# untitled.net
KiCad netlist of a schematic drawn in EAGLE
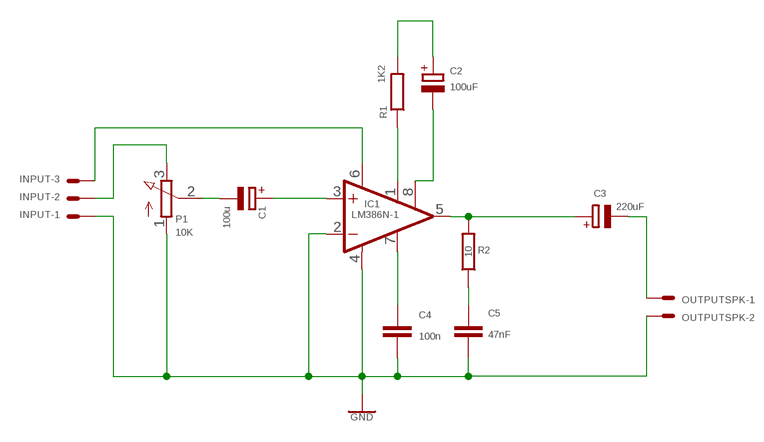
[diagram p0: schematic, sheet 1]

(export (version "E")
  (design (tool "Eeschema 10.0.6"))
  (components
    (comp (ref "C1")
      (value "100u")
      (footprint "eagle-import:E2,5-7")
      (libsource (lib "eagle-import") (part "CPOL-EUE2.5-7"))
    )
    (comp (ref "C2")
      (value "100uF")
      (footprint "eagle-import:E2,5-7")
      (libsource (lib "eagle-import") (part "CPOL-EUE2.5-7"))
    )
    (comp (ref "C3")
      (value "220uF")
      (footprint "eagle-import:E2,5-7")
      (libsource (lib "eagle-import") (part "CPOL-EUE2.5-7"))
    )
    (comp (ref "C4")
      (value "100n")
      (footprint "eagle-import:C025-025X050")
      (libsource (lib "eagle-import") (part "C-EU025-025X050"))
    )
    (comp (ref "C5")
      (value "47nF")
      (footprint "eagle-import:C025-025X050")
      (libsource (lib "eagle-import") (part "C-EU025-025X050"))
    )
    (comp (ref "IC1")
      (value "LM386N-1")
      (footprint "eagle-import:DIL08")
      (libsource (lib "eagle-import") (part "LM386?-N1"))
    )
    (comp (ref "INPUT")
      (value "22-23-2031")
      (footprint "eagle-import:22-23-2031")
      (fields (field (name "MF") "MOLEX"))
      (libsource (lib "eagle-import") (part "22-23-2031"))
    )
    (comp (ref "OUTPUTSPK")
      (value "-")
      (footprint "eagle-import:22-23-2021")
      (fields (field (name "MF") "MOLEX") (field (name "MPN") "22-23-2021"))
      (libsource (lib "eagle-import") (part "22-23-2021"))
    )
    (comp (ref "P1")
      (value "10K")
      (footprint "eagle-import:3RP_1610N")
      (libsource (lib "eagle-import") (part "3RP/1610N"))
    )
    (comp (ref "R1")
      (value "1K2")
      (footprint "eagle-import:0207_7")
      (libsource (lib "eagle-import") (part "R-EU_0207/7"))
    )
    (comp (ref "R2")
      (value "10")
      (footprint "eagle-import:0207_7")
      (libsource (lib "eagle-import") (part "R-EU_0207/7"))
    )
  )
  (nets
    (net (code "1") (name "GND") (class "Default")
      (node (ref "C4") (pin "2") (pinfunction "2_2") (pintype "passive"))
      (node (ref "C5") (pin "2") (pinfunction "2_2") (pintype "passive"))
      (node (ref "IC1") (pin "2") (pinfunction "-IN_2") (pintype "input"))
      (node (ref "IC1") (pin "4") (pinfunction "GND_4") (pintype "power_in"))
      (node (ref "INPUT") (pin "1") (pinfunction "S_1") (pintype "passive"))
      (node (ref "OUTPUTSPK") (pin "2") (pinfunction "S_2") (pintype "passive"))
      (node (ref "P1") (pin "1") (pinfunction "A_1") (pintype "passive"))
    )
    (net (code "2") (name "Net-(C2-Pad+)") (class "Default")
      (node (ref "C2") (pin "+") (pinfunction "+_+") (pintype "passive"))
      (node (ref "R1") (pin "2") (pinfunction "2_2") (pintype "passive"))
    )
    (net (code "3") (name "Net-(C2-Pad-)") (class "Default")
      (node (ref "C2") (pin "-") (pinfunction "-_-") (pintype "passive"))
      (node (ref "IC1") (pin "8") (pinfunction "GAIN_8") (pintype "passive"))
    )
    (net (code "4") (name "Net-(C5-Pad1)") (class "Default")
      (node (ref "C5") (pin "1") (pinfunction "1_1") (pintype "passive"))
      (node (ref "R2") (pin "1") (pinfunction "1_1") (pintype "passive"))
    )
    (net (code "5") (name "Net-(IC1-+IN)") (class "Default")
      (node (ref "C1") (pin "+") (pinfunction "+_+") (pintype "passive"))
      (node (ref "IC1") (pin "3") (pinfunction "+IN_3") (pintype "input"))
    )
    (net (code "6") (name "Net-(IC1-BYPASS)") (class "Default")
      (node (ref "C4") (pin "1") (pinfunction "1_1") (pintype "passive"))
      (node (ref "IC1") (pin "7") (pinfunction "BYPASS_7") (pintype "passive"))
    )
    (net (code "7") (name "Net-(IC1-GAIN-Pad1)") (class "Default")
      (node (ref "IC1") (pin "1") (pinfunction "GAIN_1") (pintype "passive"))
      (node (ref "R1") (pin "1") (pinfunction "1_1") (pintype "passive"))
    )
    (net (code "8") (name "Net-(IC1-OUT)") (class "Default")
      (node (ref "C3") (pin "+") (pinfunction "+_+") (pintype "passive"))
      (node (ref "IC1") (pin "5") (pinfunction "OUT_5") (pintype "output"))
      (node (ref "R2") (pin "2") (pinfunction "2_2") (pintype "passive"))
    )
    (net (code "9") (name "Net-(IC1-VS)") (class "Default")
      (node (ref "IC1") (pin "6") (pinfunction "VS_6") (pintype "power_in"))
      (node (ref "INPUT") (pin "3") (pinfunction "S_3") (pintype "passive"))
    )
    (net (code "10") (name "Net-(INPUTB-S)") (class "Default")
      (node (ref "INPUT") (pin "2") (pinfunction "S_2") (pintype "passive"))
      (node (ref "P1") (pin "3") (pinfunction "E_3") (pintype "passive"))
    )
    (net (code "11") (name "Net-(OUTPUTSPKA-S)") (class "Default")
      (node (ref "C3") (pin "-") (pinfunction "-_-") (pintype "passive"))
      (node (ref "OUTPUTSPK") (pin "1") (pinfunction "S_1") (pintype "passive"))
    )
    (net (code "12") (name "Net-(P1-S)") (class "Default")
      (node (ref "C1") (pin "-") (pinfunction "-_-") (pintype "passive"))
      (node (ref "P1") (pin "2") (pinfunction "S_2") (pintype "passive"))
    )
  )
)
